# Escorna_CPU_2_01.net
KiCad netlist of a schematic drawn in EAGLE
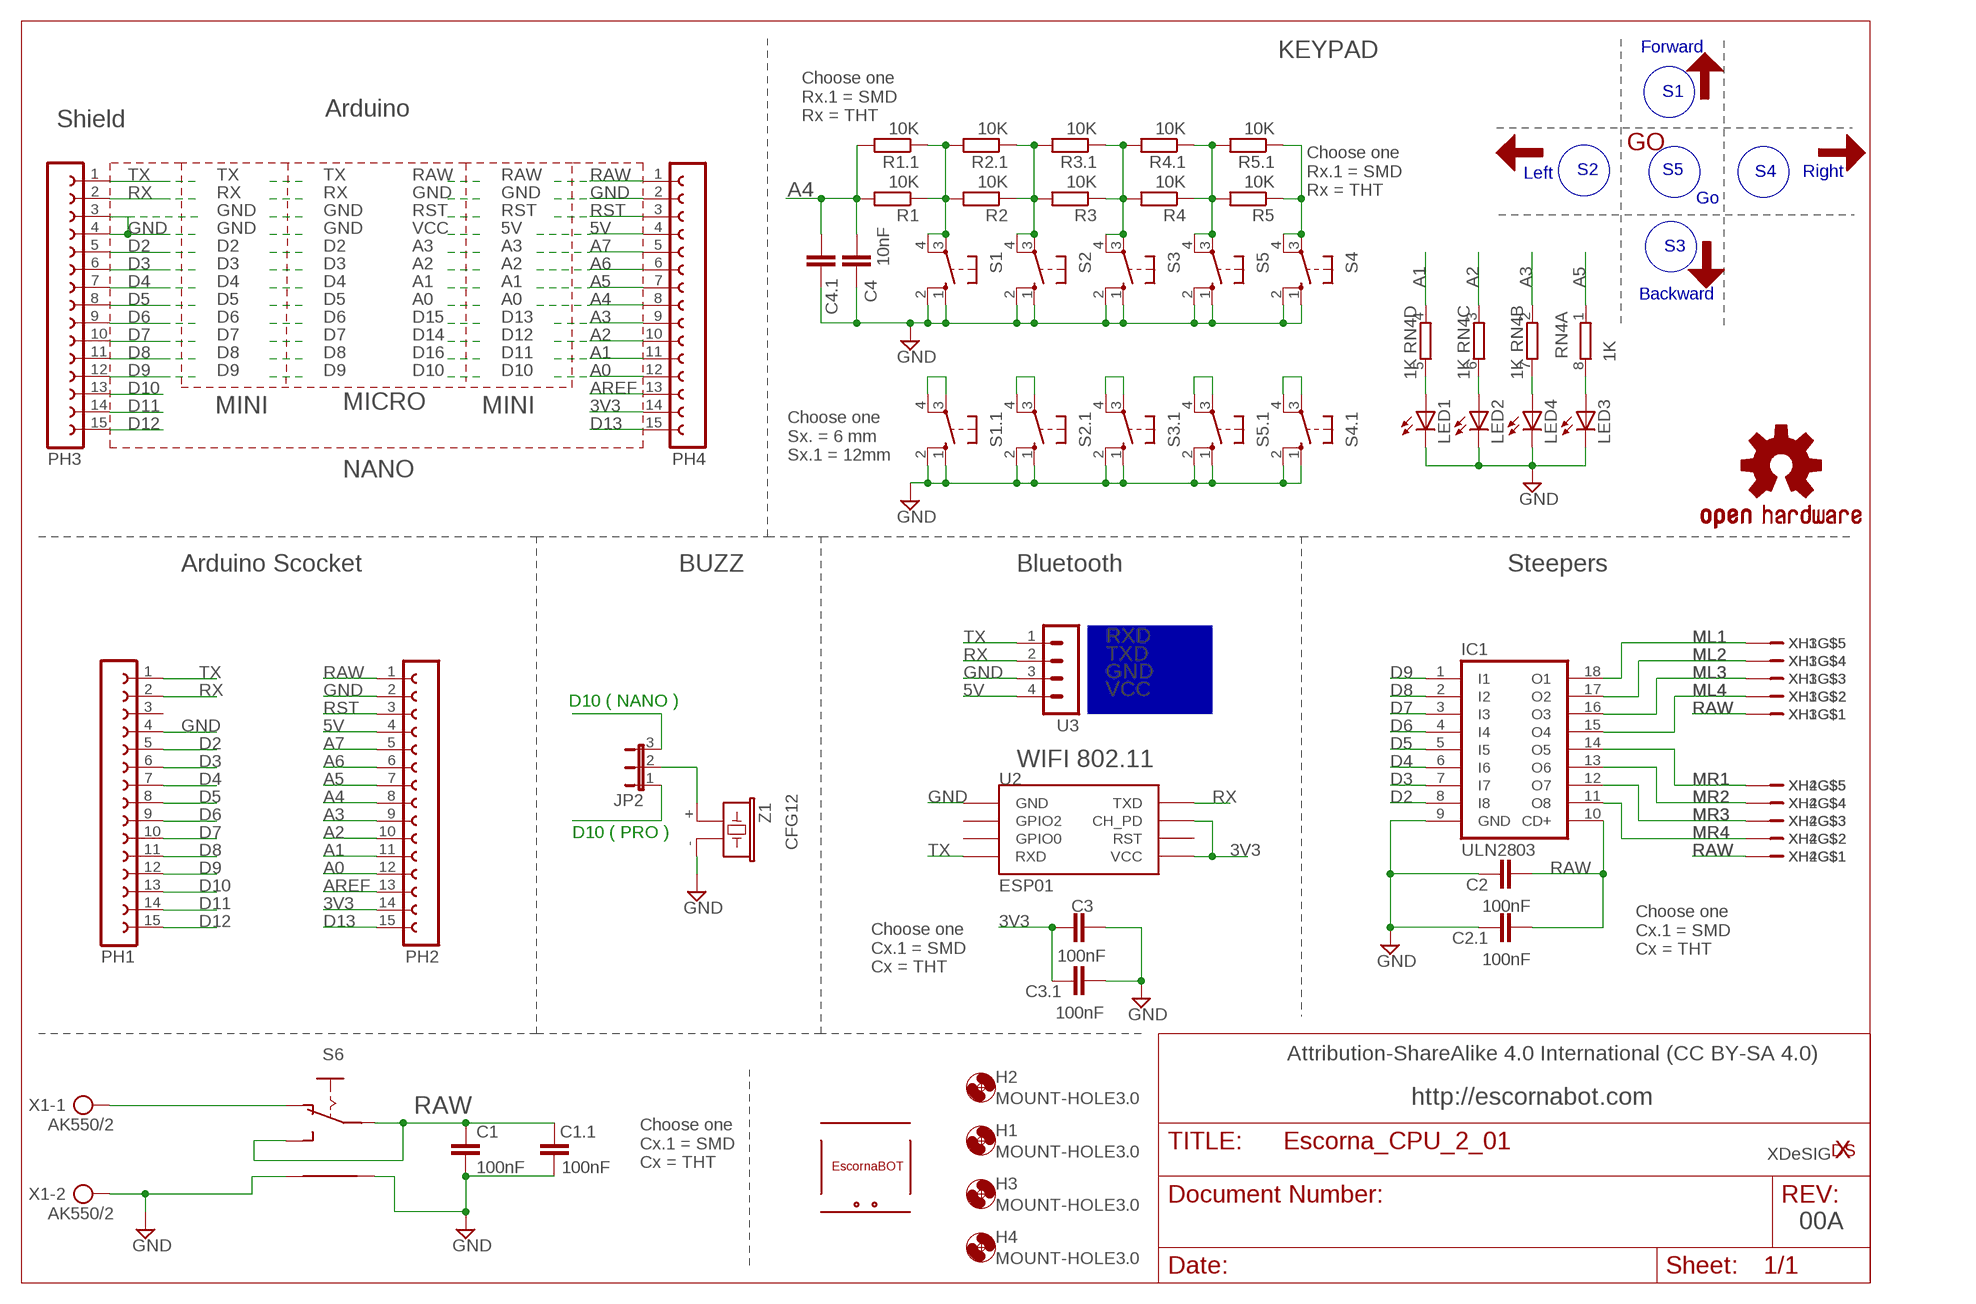
[diagram p0: schematic, sheet 1]

(export (version "E")
  (design (tool "Eeschema 10.0.6"))
  (components
    (comp (ref "C1")
      (value "100nF")
      (footprint "eagle-import:C025-025X050")
      (libsource (lib "eagle-import") (part "C-EU025-025X050"))
    )
    (comp (ref "C1.1")
      (value "100nF")
      (footprint "eagle-import:C0603")
      (libsource (lib "eagle-import") (part "C-EUC0603"))
    )
    (comp (ref "C2")
      (value "100nF")
      (footprint "eagle-import:C025-025X050")
      (libsource (lib "eagle-import") (part "C-EU025-025X050"))
    )
    (comp (ref "C2.1")
      (value "100nF")
      (footprint "eagle-import:C0603")
      (libsource (lib "eagle-import") (part "C-EUC0603"))
    )
    (comp (ref "C3")
      (value "100nF")
      (footprint "eagle-import:C025-025X050")
      (libsource (lib "eagle-import") (part "C-EU025-025X050"))
    )
    (comp (ref "C3.1")
      (value "100nF")
      (footprint "eagle-import:C0603")
      (libsource (lib "eagle-import") (part "C-EUC0603"))
    )
    (comp (ref "C4")
      (value "10nF")
      (footprint "eagle-import:C025-025X050")
      (libsource (lib "eagle-import") (part "C-EU025-025X050"))
    )
    (comp (ref "C4.1")
      (value "10nF")
      (footprint "eagle-import:C0603")
      (libsource (lib "eagle-import") (part "C-EUC0603"))
    )
    (comp (ref "ESC")
      (value "ESCORNABOT")
      (footprint "eagle-import:ESCORNA_PEQUE")
      (libsource (lib "eagle-import") (part "ESCORNABOT"))
    )
    (comp (ref "H1")
      (value "MOUNT-HOLE3.0")
      (footprint "eagle-import:3,0")
      (libsource (lib "eagle-import") (part "MOUNT-HOLE3.0"))
    )
    (comp (ref "H2")
      (value "MOUNT-HOLE3.0")
      (footprint "eagle-import:3,0")
      (libsource (lib "eagle-import") (part "MOUNT-HOLE3.0"))
    )
    (comp (ref "H3")
      (value "MOUNT-HOLE3.0")
      (footprint "eagle-import:3,0")
      (libsource (lib "eagle-import") (part "MOUNT-HOLE3.0"))
    )
    (comp (ref "H4")
      (value "MOUNT-HOLE3.0")
      (footprint "eagle-import:3,0")
      (libsource (lib "eagle-import") (part "MOUNT-HOLE3.0"))
    )
    (comp (ref "IC1")
      (value "ULN2803")
      (footprint "eagle-import:DIL18")
      (libsource (lib "eagle-import") (part "ULN2803A{dblquote}"))
    )
    (comp (ref "JP2")
      (value "JP2E")
      (footprint "eagle-import:JP2")
      (libsource (lib "eagle-import") (part "JP2E"))
    )
    (comp (ref "LED1")
      (value "LED_ESML0603")
      (footprint "eagle-import:LED_SML0603")
      (libsource (lib "eagle-import") (part "LED_ESML0603"))
    )
    (comp (ref "LED2")
      (value "LED_ESML0603")
      (footprint "eagle-import:LED_SML0603")
      (libsource (lib "eagle-import") (part "LED_ESML0603"))
    )
    (comp (ref "LED3")
      (value "LED_ESML0603")
      (footprint "eagle-import:LED_SML0603")
      (libsource (lib "eagle-import") (part "LED_ESML0603"))
    )
    (comp (ref "LED4")
      (value "LED_ESML0603")
      (footprint "eagle-import:LED_SML0603")
      (libsource (lib "eagle-import") (part "LED_ESML0603"))
    )
    (comp (ref "LOGO2")
      (value "OSHW-LOGOS")
      (footprint "eagle-import:OSHW-LOGO-S")
      (libsource (lib "eagle-import") (part "OSHW-LOGOS"))
    )
    (comp (ref "PH1")
      (value "FE15-1")
      (footprint "eagle-import:FE15")
      (libsource (lib "eagle-import") (part "FE15-1"))
    )
    (comp (ref "PH2")
      (value "FE15-1")
      (footprint "eagle-import:FE15")
      (libsource (lib "eagle-import") (part "FE15-1"))
    )
    (comp (ref "PH3")
      (value "FE15-1")
      (footprint "eagle-import:FE15")
      (libsource (lib "eagle-import") (part "FE15-1"))
    )
    (comp (ref "PH4")
      (value "FE15-1")
      (footprint "eagle-import:FE15")
      (libsource (lib "eagle-import") (part "FE15-1"))
    )
    (comp (ref "R1")
      (value "10K")
      (footprint "eagle-import:0204_7")
      (libsource (lib "eagle-import") (part "R-EU_0204/7"))
    )
    (comp (ref "R1.1")
      (value "10K")
      (footprint "eagle-import:R0603")
      (libsource (lib "eagle-import") (part "R-EU_R0603"))
    )
    (comp (ref "R2")
      (value "10K")
      (footprint "eagle-import:0204_7")
      (libsource (lib "eagle-import") (part "R-EU_0204/7"))
    )
    (comp (ref "R2.1")
      (value "10K")
      (footprint "eagle-import:R0603")
      (libsource (lib "eagle-import") (part "R-EU_R0603"))
    )
    (comp (ref "R3")
      (value "10K")
      (footprint "eagle-import:0204_7")
      (libsource (lib "eagle-import") (part "R-EU_0204/7"))
    )
    (comp (ref "R3.1")
      (value "10K")
      (footprint "eagle-import:R0603")
      (libsource (lib "eagle-import") (part "R-EU_R0603"))
    )
    (comp (ref "R4")
      (value "10K")
      (footprint "eagle-import:0204_7")
      (libsource (lib "eagle-import") (part "R-EU_0204/7"))
    )
    (comp (ref "R4.1")
      (value "10K")
      (footprint "eagle-import:R0603")
      (libsource (lib "eagle-import") (part "R-EU_R0603"))
    )
    (comp (ref "R5")
      (value "10K")
      (footprint "eagle-import:0204_7")
      (libsource (lib "eagle-import") (part "R-EU_0204/7"))
    )
    (comp (ref "R5.1")
      (value "10K")
      (footprint "eagle-import:R0603")
      (libsource (lib "eagle-import") (part "R-EU_R0603"))
    )
    (comp (ref "RN4")
      (value "1K")
      (footprint "eagle-import:CAY16")
      (libsource (lib "eagle-import") (part "4R-NCAY16"))
    )
    (comp (ref "S1")
      (value "10-XX")
      (footprint "eagle-import:B3F-10XX")
      (fields (field (name "MPN") "B3F-1000"))
      (libsource (lib "eagle-import") (part "10-XX"))
    )
    (comp (ref "S1.1")
      (value "SWITCH-OMRON_40-XX")
      (footprint "eagle-import:SWITCH-OMRON_B3F40XX_NH")
      (libsource (lib "eagle-import") (part "SWITCH-OMRON_40-XX"))
    )
    (comp (ref "S2")
      (value "10-XX")
      (footprint "eagle-import:B3F-10XX")
      (fields (field (name "MPN") "B3F-1000"))
      (libsource (lib "eagle-import") (part "10-XX"))
    )
    (comp (ref "S2.1")
      (value "SWITCH-OMRON_40-XX")
      (footprint "eagle-import:SWITCH-OMRON_B3F40XX_NH")
      (libsource (lib "eagle-import") (part "SWITCH-OMRON_40-XX"))
    )
    (comp (ref "S3")
      (value "10-XX")
      (footprint "eagle-import:B3F-10XX")
      (fields (field (name "MPN") "B3F-1000"))
      (libsource (lib "eagle-import") (part "10-XX"))
    )
    (comp (ref "S3.1")
      (value "SWITCH-OMRON_40-XX")
      (footprint "eagle-import:SWITCH-OMRON_B3F40XX_NH")
      (libsource (lib "eagle-import") (part "SWITCH-OMRON_40-XX"))
    )
    (comp (ref "S4")
      (value "10-XX")
      (footprint "eagle-import:B3F-10XX")
      (fields (field (name "MPN") "B3F-1000"))
      (libsource (lib "eagle-import") (part "10-XX"))
    )
    (comp (ref "S4.1")
      (value "SWITCH-OMRON_40-XX")
      (footprint "eagle-import:SWITCH-OMRON_B3F40XX_NH")
      (libsource (lib "eagle-import") (part "SWITCH-OMRON_40-XX"))
    )
    (comp (ref "S5")
      (value "10-XX")
      (footprint "eagle-import:B3F-10XX")
      (fields (field (name "MPN") "B3F-1000"))
      (libsource (lib "eagle-import") (part "10-XX"))
    )
    (comp (ref "S5.1")
      (value "SWITCH-OMRON_40-XX")
      (footprint "eagle-import:SWITCH-OMRON_B3F40XX_NH")
      (libsource (lib "eagle-import") (part "SWITCH-OMRON_40-XX"))
    )
    (comp (ref "S6")
      (value "SK12F14D")
      (footprint "eagle-import:SK-12D07")
      (libsource (lib "eagle-import") (part "SK12F14D"))
    )
    (comp (ref "U$1")
      (value "FRECHA")
      (footprint "eagle-import:FRECHA")
      (libsource (lib "eagle-import") (part "FRECHA"))
    )
    (comp (ref "U$2")
      (value "GO")
      (footprint "eagle-import:VALE")
      (libsource (lib "eagle-import") (part "GO"))
    )
    (comp (ref "U$3")
      (value "FRECHA")
      (footprint "eagle-import:FRECHA")
      (libsource (lib "eagle-import") (part "FRECHA"))
    )
    (comp (ref "U$6")
      (value "FRECHA")
      (footprint "eagle-import:FRECHA")
      (libsource (lib "eagle-import") (part "FRECHA"))
    )
    (comp (ref "U$11")
      (value "FRECHA")
      (footprint "eagle-import:FRECHA")
      (libsource (lib "eagle-import") (part "FRECHA"))
    )
    (comp (ref "U2")
      (value "ESP01")
      (footprint "eagle-import:ESP01")
      (libsource (lib "eagle-import") (part "ESP01"))
    )
    (comp (ref "U3")
      (value "MA04-1")
      (footprint "eagle-import:MA04-1")
      (libsource (lib "eagle-import") (part "MA04-1"))
    )
    (comp (ref "X1")
      (value "AK550/2")
      (footprint "eagle-import:AK550_2")
      (libsource (lib "eagle-import") (part "AK550/2"))
    )
    (comp (ref "XDS1")
      (value "XDESIG")
      (footprint "eagle-import:XDESIG_CU_2")
      (libsource (lib "eagle-import") (part "XDESIG"))
    )
    (comp (ref "XH1")
      (value "B5B-XH-A")
      (footprint "eagle-import:B5B-XH-A")
      (libsource (lib "eagle-import") (part "B5B-XH-A"))
    )
    (comp (ref "XH2")
      (value "B5B-XH-A")
      (footprint "eagle-import:B5B-XH-A")
      (libsource (lib "eagle-import") (part "B5B-XH-A"))
    )
    (comp (ref "XH3")
      (value "B5B-XH-A")
      (footprint "eagle-import:B5B-XH-A")
      (libsource (lib "eagle-import") (part "B5B-XH-A"))
    )
    (comp (ref "XH4")
      (value "B5B-XH-A")
      (footprint "eagle-import:B5B-XH-A")
      (libsource (lib "eagle-import") (part "B5B-XH-A"))
    )
    (comp (ref "Z1")
      (value "CFG12")
      (footprint "eagle-import:F_CM12P")
      (libsource (lib "eagle-import") (part "F/CM12P"))
    )
  )
  (nets
    (net (code "1") (name "/3V3") (class "Default")
      (node (ref "C3") (pin "1") (pinfunction "1_1") (pintype "passive"))
      (node (ref "C3.1") (pin "1") (pinfunction "1_1") (pintype "passive"))
      (node (ref "PH2") (pin "14") (pinfunction "14_14") (pintype "passive"))
      (node (ref "PH4") (pin "14") (pinfunction "14_14") (pintype "passive"))
      (node (ref "U2") (pin "CH_PD") (pinfunction "CH_PD_CH_PD") (pintype "bidirectional"))
      (node (ref "U2") (pin "VCC") (pinfunction "VCC_VCC") (pintype "bidirectional"))
    )
    (net (code "2") (name "/5V") (class "Default")
      (node (ref "PH2") (pin "4") (pinfunction "4_4") (pintype "passive"))
      (node (ref "PH4") (pin "4") (pinfunction "4_4") (pintype "passive"))
      (node (ref "U3") (pin "4") (pinfunction "4_4") (pintype "passive"))
    )
    (net (code "3") (name "/A0") (class "Default")
      (node (ref "JP2") (pin "1") (pinfunction "1_1") (pintype "passive"))
      (node (ref "PH2") (pin "12") (pinfunction "12_12") (pintype "passive"))
      (node (ref "PH4") (pin "12") (pinfunction "12_12") (pintype "passive"))
    )
    (net (code "4") (name "/A1") (class "Default")
      (node (ref "PH2") (pin "11") (pinfunction "11_11") (pintype "passive"))
      (node (ref "PH4") (pin "11") (pinfunction "11_11") (pintype "passive"))
      (node (ref "RN4") (pin "4") (pinfunction "1_4") (pintype "passive"))
    )
    (net (code "5") (name "/A2") (class "Default")
      (node (ref "PH2") (pin "10") (pinfunction "10_10") (pintype "passive"))
      (node (ref "PH4") (pin "10") (pinfunction "10_10") (pintype "passive"))
      (node (ref "RN4") (pin "3") (pinfunction "1_3") (pintype "passive"))
    )
    (net (code "6") (name "/A3") (class "Default")
      (node (ref "PH2") (pin "9") (pinfunction "9_9") (pintype "passive"))
      (node (ref "PH4") (pin "9") (pinfunction "9_9") (pintype "passive"))
      (node (ref "RN4") (pin "2") (pinfunction "1_2") (pintype "passive"))
    )
    (net (code "7") (name "/A4") (class "Default")
      (node (ref "C4") (pin "2") (pinfunction "2_2") (pintype "passive"))
      (node (ref "C4.1") (pin "2") (pinfunction "2_2") (pintype "passive"))
      (node (ref "PH2") (pin "8") (pinfunction "8_8") (pintype "passive"))
      (node (ref "PH4") (pin "8") (pinfunction "8_8") (pintype "passive"))
      (node (ref "R1") (pin "2") (pinfunction "2_2") (pintype "passive"))
      (node (ref "R1.1") (pin "2") (pinfunction "2_2") (pintype "passive"))
    )
    (net (code "8") (name "/A5") (class "Default")
      (node (ref "PH2") (pin "7") (pinfunction "7_7") (pintype "passive"))
      (node (ref "PH4") (pin "7") (pinfunction "7_7") (pintype "passive"))
      (node (ref "RN4") (pin "1") (pinfunction "1_1") (pintype "passive"))
    )
    (net (code "9") (name "/A6") (class "Default")
      (node (ref "PH2") (pin "6") (pinfunction "6_6") (pintype "passive"))
      (node (ref "PH4") (pin "6") (pinfunction "6_6") (pintype "passive"))
    )
    (net (code "10") (name "/A7") (class "Default")
      (node (ref "PH2") (pin "5") (pinfunction "5_5") (pintype "passive"))
      (node (ref "PH4") (pin "5") (pinfunction "5_5") (pintype "passive"))
    )
    (net (code "11") (name "/AREF") (class "Default")
      (node (ref "PH2") (pin "13") (pinfunction "13_13") (pintype "passive"))
      (node (ref "PH4") (pin "13") (pinfunction "13_13") (pintype "passive"))
    )
    (net (code "12") (name "/D2") (class "Default")
      (node (ref "IC1") (pin "8") (pinfunction "I8_8") (pintype "input"))
      (node (ref "PH1") (pin "5") (pinfunction "5_5") (pintype "passive"))
      (node (ref "PH3") (pin "5") (pinfunction "5_5") (pintype "passive"))
    )
    (net (code "13") (name "/D3") (class "Default")
      (node (ref "IC1") (pin "7") (pinfunction "I7_7") (pintype "input"))
      (node (ref "PH1") (pin "6") (pinfunction "6_6") (pintype "passive"))
      (node (ref "PH3") (pin "6") (pinfunction "6_6") (pintype "passive"))
    )
    (net (code "14") (name "/D4") (class "Default")
      (node (ref "IC1") (pin "6") (pinfunction "I6_6") (pintype "input"))
      (node (ref "PH1") (pin "7") (pinfunction "7_7") (pintype "passive"))
      (node (ref "PH3") (pin "7") (pinfunction "7_7") (pintype "passive"))
    )
    (net (code "15") (name "/D5") (class "Default")
      (node (ref "IC1") (pin "5") (pinfunction "I5_5") (pintype "input"))
      (node (ref "PH1") (pin "8") (pinfunction "8_8") (pintype "passive"))
      (node (ref "PH3") (pin "8") (pinfunction "8_8") (pintype "passive"))
    )
    (net (code "16") (name "/D6") (class "Default")
      (node (ref "IC1") (pin "4") (pinfunction "I4_4") (pintype "input"))
      (node (ref "PH1") (pin "9") (pinfunction "9_9") (pintype "passive"))
      (node (ref "PH3") (pin "9") (pinfunction "9_9") (pintype "passive"))
    )
    (net (code "17") (name "/D7") (class "Default")
      (node (ref "IC1") (pin "3") (pinfunction "I3_3") (pintype "input"))
      (node (ref "PH1") (pin "10") (pinfunction "10_10") (pintype "passive"))
      (node (ref "PH3") (pin "10") (pinfunction "10_10") (pintype "passive"))
    )
    (net (code "18") (name "/D8") (class "Default")
      (node (ref "IC1") (pin "2") (pinfunction "I2_2") (pintype "input"))
      (node (ref "PH1") (pin "11") (pinfunction "11_11") (pintype "passive"))
      (node (ref "PH3") (pin "11") (pinfunction "11_11") (pintype "passive"))
    )
    (net (code "19") (name "/D9") (class "Default")
      (node (ref "IC1") (pin "1") (pinfunction "I1_1") (pintype "input"))
      (node (ref "PH1") (pin "12") (pinfunction "12_12") (pintype "passive"))
      (node (ref "PH3") (pin "12") (pinfunction "12_12") (pintype "passive"))
    )
    (net (code "20") (name "/D10") (class "Default")
      (node (ref "JP2") (pin "3") (pinfunction "3_3") (pintype "passive"))
      (node (ref "PH1") (pin "13") (pinfunction "13_13") (pintype "passive"))
      (node (ref "PH3") (pin "13") (pinfunction "13_13") (pintype "passive"))
    )
    (net (code "21") (name "/D11") (class "Default")
      (node (ref "PH1") (pin "14") (pinfunction "14_14") (pintype "passive"))
      (node (ref "PH3") (pin "14") (pinfunction "14_14") (pintype "passive"))
    )
    (net (code "22") (name "/D12") (class "Default")
      (node (ref "PH1") (pin "15") (pinfunction "15_15") (pintype "passive"))
      (node (ref "PH3") (pin "15") (pinfunction "15_15") (pintype "passive"))
    )
    (net (code "23") (name "/D13") (class "Default")
      (node (ref "PH2") (pin "15") (pinfunction "15_15") (pintype "passive"))
      (node (ref "PH4") (pin "15") (pinfunction "15_15") (pintype "passive"))
    )
    (net (code "24") (name "/ML1") (class "Default")
      (node (ref "IC1") (pin "18") (pinfunction "O1_18") (pintype "open_collector"))
      (node (ref "XH1") (pin "P$5") (pinfunction "1_P$5") (pintype "passive"))
      (node (ref "XH3") (pin "P$5") (pinfunction "1_P$5") (pintype "passive"))
    )
    (net (code "25") (name "/ML2") (class "Default")
      (node (ref "IC1") (pin "17") (pinfunction "O2_17") (pintype "open_collector"))
      (node (ref "XH1") (pin "P$4") (pinfunction "1_P$4") (pintype "passive"))
      (node (ref "XH3") (pin "P$4") (pinfunction "1_P$4") (pintype "passive"))
    )
    (net (code "26") (name "/ML3") (class "Default")
      (node (ref "IC1") (pin "16") (pinfunction "O3_16") (pintype "open_collector"))
      (node (ref "XH1") (pin "P$3") (pinfunction "1_P$3") (pintype "passive"))
      (node (ref "XH3") (pin "P$3") (pinfunction "1_P$3") (pintype "passive"))
    )
    (net (code "27") (name "/ML4") (class "Default")
      (node (ref "IC1") (pin "15") (pinfunction "O4_15") (pintype "open_collector"))
      (node (ref "XH1") (pin "P$2") (pinfunction "1_P$2") (pintype "passive"))
      (node (ref "XH3") (pin "P$2") (pinfunction "1_P$2") (pintype "passive"))
    )
    (net (code "28") (name "/MR1") (class "Default")
      (node (ref "IC1") (pin "14") (pinfunction "O5_14") (pintype "open_collector"))
      (node (ref "XH2") (pin "P$5") (pinfunction "1_P$5") (pintype "passive"))
      (node (ref "XH4") (pin "P$5") (pinfunction "1_P$5") (pintype "passive"))
    )
    (net (code "29") (name "/MR2") (class "Default")
      (node (ref "IC1") (pin "13") (pinfunction "O6_13") (pintype "open_collector"))
      (node (ref "XH2") (pin "P$4") (pinfunction "1_P$4") (pintype "passive"))
      (node (ref "XH4") (pin "P$4") (pinfunction "1_P$4") (pintype "passive"))
    )
    (net (code "30") (name "/MR3") (class "Default")
      (node (ref "IC1") (pin "12") (pinfunction "O7_12") (pintype "open_collector"))
      (node (ref "XH2") (pin "P$3") (pinfunction "1_P$3") (pintype "passive"))
      (node (ref "XH4") (pin "P$3") (pinfunction "1_P$3") (pintype "passive"))
    )
    (net (code "31") (name "/MR4") (class "Default")
      (node (ref "IC1") (pin "11") (pinfunction "O8_11") (pintype "open_collector"))
      (node (ref "XH2") (pin "P$2") (pinfunction "1_P$2") (pintype "passive"))
      (node (ref "XH4") (pin "P$2") (pinfunction "1_P$2") (pintype "passive"))
    )
    (net (code "32") (name "/RAW") (class "Default")
      (node (ref "C1") (pin "1") (pinfunction "1_1") (pintype "passive"))
      (node (ref "C1.1") (pin "2") (pinfunction "2_2") (pintype "passive"))
      (node (ref "C2") (pin "2") (pinfunction "2_2") (pintype "passive"))
      (node (ref "C2.1") (pin "2") (pinfunction "2_2") (pintype "passive"))
      (node (ref "IC1") (pin "10") (pinfunction "CD+_10") (pintype "passive"))
      (node (ref "PH2") (pin "1") (pinfunction "1_1") (pintype "passive"))
      (node (ref "PH4") (pin "1") (pinfunction "1_1") (pintype "passive"))
      (node (ref "S6") (pin "P$1") (pinfunction "P_P$1") (pintype "passive"))
      (node (ref "S6") (pin "P$3") (pinfunction "S_P$3") (pintype "passive"))
      (node (ref "XH1") (pin "P$1") (pinfunction "1_P$1") (pintype "passive"))
      (node (ref "XH2") (pin "P$1") (pinfunction "1_P$1") (pintype "passive"))
      (node (ref "XH3") (pin "P$1") (pinfunction "1_P$1") (pintype "passive"))
      (node (ref "XH4") (pin "P$1") (pinfunction "1_P$1") (pintype "passive"))
    )
    (net (code "33") (name "/RST") (class "Default")
      (node (ref "PH2") (pin "3") (pinfunction "3_3") (pintype "passive"))
      (node (ref "PH4") (pin "3") (pinfunction "3_3") (pintype "passive"))
    )
    (net (code "34") (name "/RX") (class "Default")
      (node (ref "PH1") (pin "2") (pinfunction "2_2") (pintype "passive"))
      (node (ref "PH3") (pin "2") (pinfunction "2_2") (pintype "passive"))
      (node (ref "U2") (pin "TX") (pinfunction "TXD_TX") (pintype "bidirectional"))
      (node (ref "U3") (pin "2") (pinfunction "2_2") (pintype "passive"))
    )
    (net (code "35") (name "/S1") (class "Default")
      (node (ref "R1") (pin "1") (pinfunction "1_1") (pintype "passive"))
      (node (ref "R1.1") (pin "1") (pinfunction "1_1") (pintype "passive"))
      (node (ref "R2") (pin "2") (pinfunction "2_2") (pintype "passive"))
      (node (ref "R2.1") (pin "2") (pinfunction "2_2") (pintype "passive"))
      (node (ref "S1") (pin "3") (pinfunction "P_3") (pintype "passive"))
      (node (ref "S1") (pin "4") (pinfunction "P1_4") (pintype "passive"))
      (node (ref "S1.1") (pin "3") (pinfunction "P_3") (pintype "passive"))
      (node (ref "S1.1") (pin "4") (pinfunction "P1_4") (pintype "passive"))
    )
    (net (code "36") (name "/S2") (class "Default")
      (node (ref "R2") (pin "1") (pinfunction "1_1") (pintype "passive"))
      (node (ref "R2.1") (pin "1") (pinfunction "1_1") (pintype "passive"))
      (node (ref "R3") (pin "2") (pinfunction "2_2") (pintype "passive"))
      (node (ref "R3.1") (pin "2") (pinfunction "2_2") (pintype "passive"))
      (node (ref "S2") (pin "3") (pinfunction "P_3") (pintype "passive"))
      (node (ref "S2") (pin "4") (pinfunction "P1_4") (pintype "passive"))
      (node (ref "S2.1") (pin "3") (pinfunction "P_3") (pintype "passive"))
      (node (ref "S2.1") (pin "4") (pinfunction "P1_4") (pintype "passive"))
    )
    (net (code "37") (name "/S3") (class "Default")
      (node (ref "R3") (pin "1") (pinfunction "1_1") (pintype "passive"))
      (node (ref "R3.1") (pin "1") (pinfunction "1_1") (pintype "passive"))
      (node (ref "R4") (pin "2") (pinfunction "2_2") (pintype "passive"))
      (node (ref "R4.1") (pin "2") (pinfunction "2_2") (pintype "passive"))
      (node (ref "S3") (pin "3") (pinfunction "P_3") (pintype "passive"))
      (node (ref "S3") (pin "4") (pinfunction "P1_4") (pintype "passive"))
      (node (ref "S3.1") (pin "3") (pinfunction "P_3") (pintype "passive"))
      (node (ref "S3.1") (pin "4") (pinfunction "P1_4") (pintype "passive"))
    )
    (net (code "38") (name "/S4") (class "Default")
      (node (ref "R4") (pin "1") (pinfunction "1_1") (pintype "passive"))
      (node (ref "R4.1") (pin "1") (pinfunction "1_1") (pintype "passive"))
      (node (ref "R5") (pin "2") (pinfunction "2_2") (pintype "passive"))
      (node (ref "R5.1") (pin "2") (pinfunction "2_2") (pintype "passive"))
      (node (ref "S5") (pin "3") (pinfunction "P_3") (pintype "passive"))
      (node (ref "S5") (pin "4") (pinfunction "P1_4") (pintype "passive"))
      (node (ref "S5.1") (pin "3") (pinfunction "P_3") (pintype "passive"))
      (node (ref "S5.1") (pin "4") (pinfunction "P1_4") (pintype "passive"))
    )
    (net (code "39") (name "/S5") (class "Default")
      (node (ref "R5") (pin "1") (pinfunction "1_1") (pintype "passive"))
      (node (ref "R5.1") (pin "1") (pinfunction "1_1") (pintype "passive"))
      (node (ref "S4") (pin "3") (pinfunction "P_3") (pintype "passive"))
      (node (ref "S4") (pin "4") (pinfunction "P1_4") (pintype "passive"))
      (node (ref "S4.1") (pin "3") (pinfunction "P_3") (pintype "passive"))
      (node (ref "S4.1") (pin "4") (pinfunction "P1_4") (pintype "passive"))
    )
    (net (code "40") (name "/TX") (class "Default")
      (node (ref "PH1") (pin "1") (pinfunction "1_1") (pintype "passive"))
      (node (ref "PH3") (pin "1") (pinfunction "1_1") (pintype "passive"))
      (node (ref "U2") (pin "RX") (pinfunction "RXD_RX") (pintype "bidirectional"))
      (node (ref "U3") (pin "1") (pinfunction "1_1") (pintype "passive"))
    )
    (net (code "41") (name "GND") (class "Default")
      (node (ref "C1") (pin "2") (pinfunction "2_2") (pintype "passive"))
      (node (ref "C1.1") (pin "1") (pinfunction "1_1") (pintype "passive"))
      (node (ref "C2") (pin "1") (pinfunction "1_1") (pintype "passive"))
      (node (ref "C2.1") (pin "1") (pinfunction "1_1") (pintype "passive"))
      (node (ref "C3") (pin "2") (pinfunction "2_2") (pintype "passive"))
      (node (ref "C3.1") (pin "2") (pinfunction "2_2") (pintype "passive"))
      (node (ref "C4") (pin "1") (pinfunction "1_1") (pintype "passive"))
      (node (ref "C4.1") (pin "1") (pinfunction "1_1") (pintype "passive"))
      (node (ref "IC1") (pin "9") (pinfunction "GND_9") (pintype "power_in"))
      (node (ref "LED1") (pin "C") (pinfunction "C_C") (pintype "passive"))
      (node (ref "LED2") (pin "C") (pinfunction "C_C") (pintype "passive"))
      (node (ref "LED3") (pin "C") (pinfunction "C_C") (pintype "passive"))
      (node (ref "LED4") (pin "C") (pinfunction "C_C") (pintype "passive"))
      (node (ref "PH1") (pin "4") (pinfunction "4_4") (pintype "passive"))
      (node (ref "PH2") (pin "2") (pinfunction "2_2") (pintype "passive"))
      (node (ref "PH3") (pin "3") (pinfunction "3_3") (pintype "passive"))
      (node (ref "PH3") (pin "4") (pinfunction "4_4") (pintype "passive"))
      (node (ref "PH4") (pin "2") (pinfunction "2_2") (pintype "passive"))
      (node (ref "S1") (pin "1") (pinfunction "S_1") (pintype "passive"))
      (node (ref "S1") (pin "2") (pinfunction "S1_2") (pintype "passive"))
      (node (ref "S1.1") (pin "1") (pinfunction "S_1") (pintype "passive"))
      (node (ref "S1.1") (pin "2") (pinfunction "S1_2") (pintype "passive"))
      (node (ref "S2") (pin "1") (pinfunction "S_1") (pintype "passive"))
      (node (ref "S2") (pin "2") (pinfunction "S1_2") (pintype "passive"))
      (node (ref "S2.1") (pin "1") (pinfunction "S_1") (pintype "passive"))
      (node (ref "S2.1") (pin "2") (pinfunction "S1_2") (pintype "passive"))
      (node (ref "S3") (pin "1") (pinfunction "S_1") (pintype "passive"))
      (node (ref "S3") (pin "2") (pinfunction "S1_2") (pintype "passive"))
      (node (ref "S3.1") (pin "1") (pinfunction "S_1") (pintype "passive"))
      (node (ref "S3.1") (pin "2") (pinfunction "S1_2") (pintype "passive"))
      (node (ref "S4") (pin "1") (pinfunction "S_1") (pintype "passive"))
      (node (ref "S4") (pin "2") (pinfunction "S1_2") (pintype "passive"))
      (node (ref "S4.1") (pin "1") (pinfunction "S_1") (pintype "passive"))
      (node (ref "S4.1") (pin "2") (pinfunction "S1_2") (pintype "passive"))
      (node (ref "S5") (pin "1") (pinfunction "S_1") (pintype "passive"))
      (node (ref "S5") (pin "2") (pinfunction "S1_2") (pintype "passive"))
      (node (ref "S5.1") (pin "1") (pinfunction "S_1") (pintype "passive"))
      (node (ref "S5.1") (pin "2") (pinfunction "S1_2") (pintype "passive"))
      (node (ref "S6") (pin "P$4") (pinfunction "P$1_P$4") (pintype "passive"))
      (node (ref "S6") (pin "P$5") (pinfunction "P$2_P$5") (pintype "bidirectional"))
      (node (ref "U2") (pin "GND") (pinfunction "GND_GND") (pintype "bidirectional"))
      (node (ref "U3") (pin "3") (pinfunction "3_3") (pintype "passive"))
      (node (ref "X1") (pin "2") (pinfunction "KL_2") (pintype "passive"))
      (node (ref "Z1") (pin "-") (pinfunction "2_-") (pintype "passive"))
    )
    (net (code "42") (name "Net-(RN4A-2)") (class "Default")
      (node (ref "LED3") (pin "A") (pinfunction "A_A") (pintype "passive"))
      (node (ref "RN4") (pin "8") (pinfunction "2_8") (pintype "passive"))
    )
    (net (code "43") (name "Net-(RN4B-2)") (class "Default")
      (node (ref "LED4") (pin "A") (pinfunction "A_A") (pintype "passive"))
      (node (ref "RN4") (pin "7") (pinfunction "2_7") (pintype "passive"))
    )
    (net (code "44") (name "Net-(RN4C-2)") (class "Default")
      (node (ref "LED2") (pin "A") (pinfunction "A_A") (pintype "passive"))
      (node (ref "RN4") (pin "6") (pinfunction "2_6") (pintype "passive"))
    )
    (net (code "45") (name "Net-(RN4D-2)") (class "Default")
      (node (ref "LED1") (pin "A") (pinfunction "A_A") (pintype "passive"))
      (node (ref "RN4") (pin "5") (pinfunction "2_5") (pintype "passive"))
    )
    (net (code "46") (name "Net-(S6-O)") (class "Default")
      (node (ref "S6") (pin "P$2") (pinfunction "O_P$2") (pintype "passive"))
      (node (ref "X1") (pin "1") (pinfunction "KL_1") (pintype "passive"))
    )
    (net (code "47") (name "Net-(Z1-1)") (class "Default")
      (node (ref "JP2") (pin "2") (pinfunction "2_2") (pintype "passive"))
      (node (ref "Z1") (pin "+") (pinfunction "1_+") (pintype "passive"))
    )
    (net (code "48") (name "unconnected-(PH1-Pad3)") (class "Default")
      (node (ref "PH1") (pin "3") (pinfunction "3_3") (pintype "passive"))
    )
    (net (code "49") (name "unconnected-(U2-PadGPIO0)") (class "Default")
      (node (ref "U2") (pin "GPIO0") (pinfunction "GPIO0_GPIO0") (pintype "bidirectional"))
    )
    (net (code "50") (name "unconnected-(U2-PadGPIO2)") (class "Default")
      (node (ref "U2") (pin "GPIO2") (pinfunction "GPIO2_GPIO2") (pintype "bidirectional"))
    )
    (net (code "51") (name "unconnected-(U2-PadRST)") (class "Default")
      (node (ref "U2") (pin "RST") (pinfunction "RST_RST") (pintype "bidirectional"))
    )
  )
)
